# dashboard-pcbsch_aveon.net
KiCad netlist of a schematic drawn in EAGLE
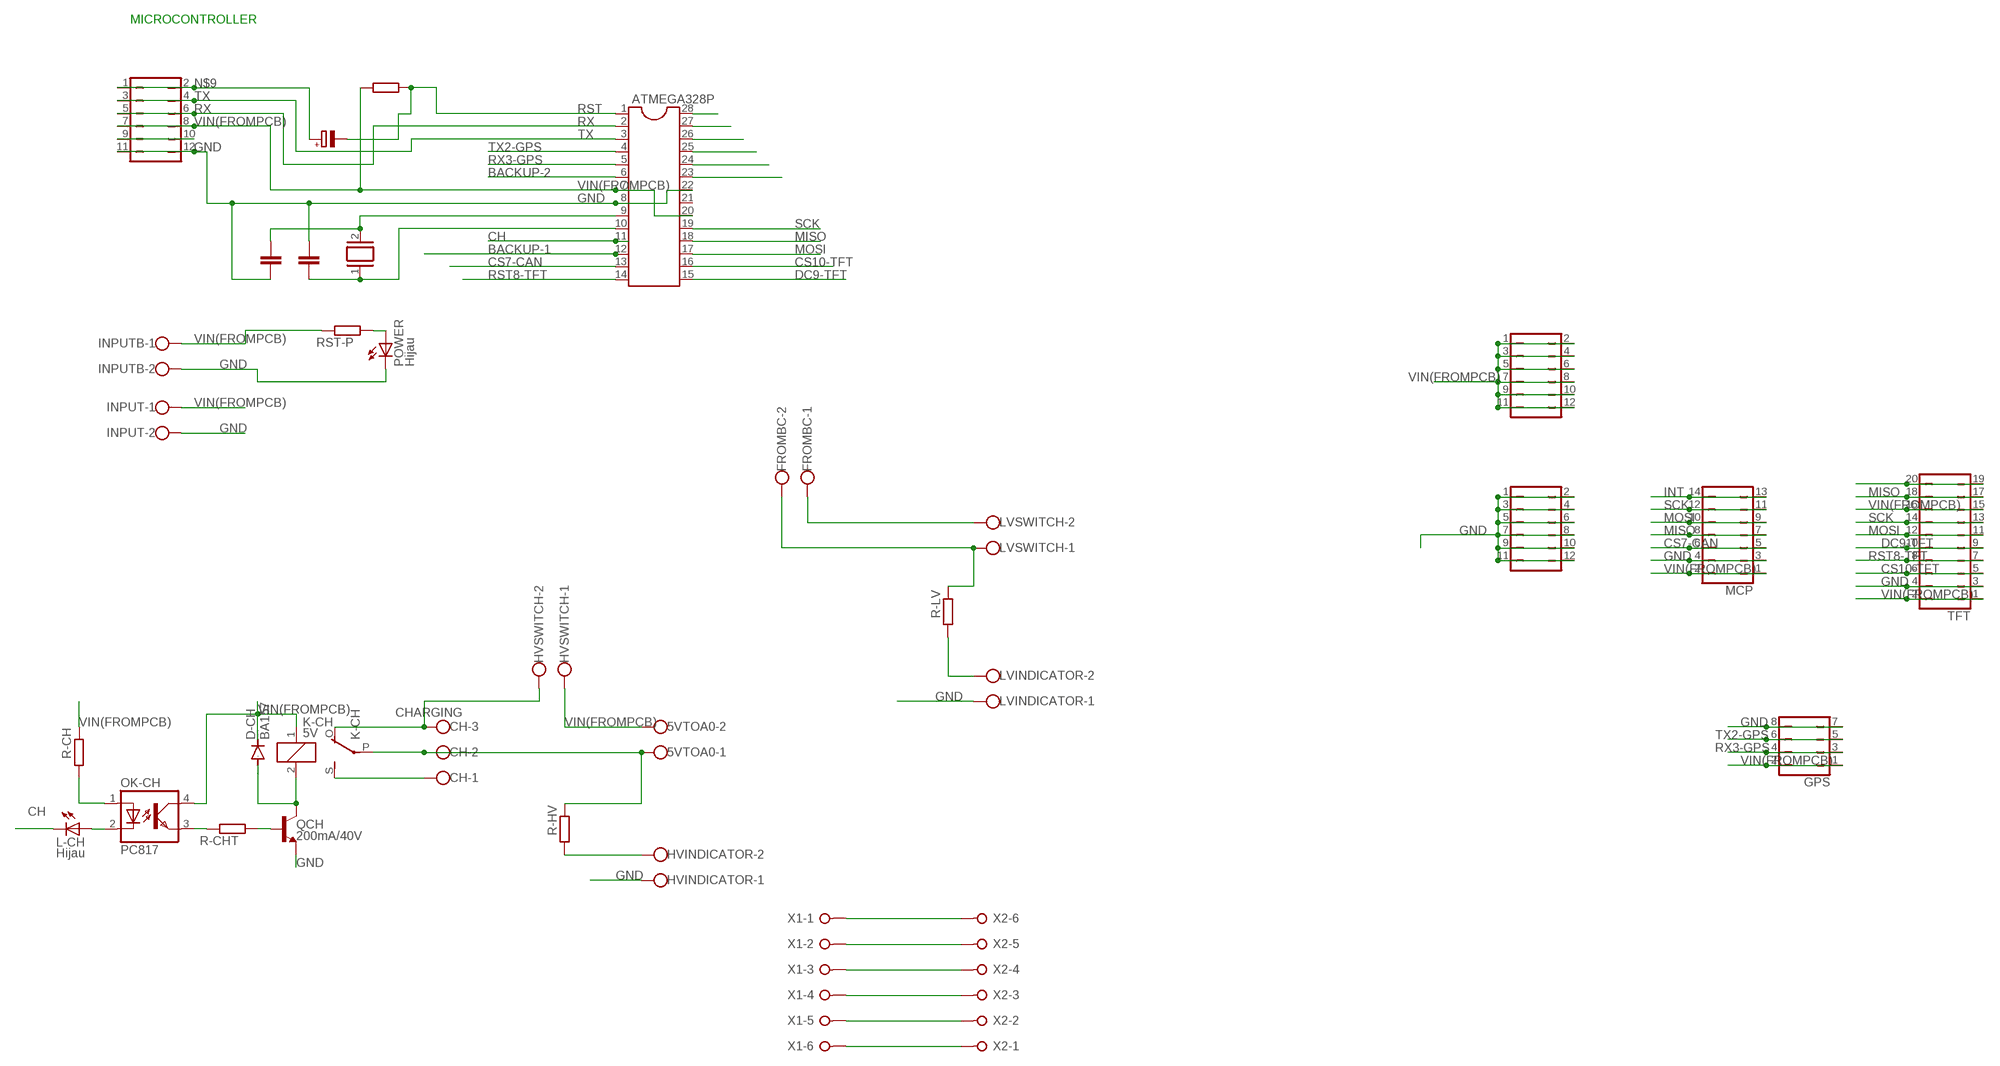
[diagram p0: schematic, sheet 1]

(export (version "E")
  (design (tool "Eeschema 10.0.6"))
  (components
    (comp (ref "5VTOA0")
      (value "W237-102")
      (footprint "eagle-import:W237-102")
      (fields (field (name "MPN") "237-102"))
      (libsource (lib "eagle-import") (part "W237-102"))
    )
    (comp (ref "ATMEGA328P")
      (value "DIL28-3")
      (footprint "eagle-import:DIL28-3")
      (libsource (lib "eagle-import") (part "DIL28-3"))
    )
    (comp (ref "C1")
      (value "C-EU025-030X050")
      (footprint "eagle-import:C025-030X050")
      (libsource (lib "eagle-import") (part "C-EU025-030X050"))
    )
    (comp (ref "C2")
      (value "C-EU025-030X050")
      (footprint "eagle-import:C025-030X050")
      (libsource (lib "eagle-import") (part "C-EU025-030X050"))
    )
    (comp (ref "CH")
      (value "CHARGING")
      (footprint "eagle-import:W237-103")
      (fields (field (name "MPN") "237-103"))
      (libsource (lib "eagle-import") (part "W237-103"))
    )
    (comp (ref "CRYSTAL")
      (value "XTAL/S")
      (footprint "eagle-import:QS")
      (libsource (lib "eagle-import") (part "XTAL/S"))
    )
    (comp (ref "D-CH")
      (value "BA157")
      (footprint "eagle-import:P1-10")
      (libsource (lib "eagle-import") (part "BA157"))
    )
    (comp (ref "FROMBC")
      (value "W237-102")
      (footprint "eagle-import:W237-102")
      (fields (field (name "MPN") "237-102"))
      (libsource (lib "eagle-import") (part "W237-102"))
    )
    (comp (ref "GPS")
      (value "JP4Q")
      (footprint "eagle-import:JP4Q")
      (libsource (lib "eagle-import") (part "JP4Q"))
    )
    (comp (ref "GROUND")
      (value "JP6Q")
      (footprint "eagle-import:JP6Q")
      (libsource (lib "eagle-import") (part "JP6Q"))
    )
    (comp (ref "HVINDICATOR")
      (value "W237-102")
      (footprint "eagle-import:W237-102")
      (fields (field (name "MPN") "237-102"))
      (libsource (lib "eagle-import") (part "W237-102"))
    )
    (comp (ref "HVSWITCH")
      (value "W237-102")
      (footprint "eagle-import:W237-102")
      (fields (field (name "MPN") "237-102"))
      (libsource (lib "eagle-import") (part "W237-102"))
    )
    (comp (ref "INPUT")
      (value "W237-102")
      (footprint "eagle-import:W237-102")
      (fields (field (name "MPN") "237-102"))
      (libsource (lib "eagle-import") (part "W237-102"))
    )
    (comp (ref "INPUTB")
      (value "W237-102")
      (footprint "eagle-import:W237-102")
      (fields (field (name "MPN") "237-102"))
      (libsource (lib "eagle-import") (part "W237-102"))
    )
    (comp (ref "K-CH")
      (value "5V")
      (footprint "eagle-import:ZF112")
      (libsource (lib "eagle-import") (part "ZF112"))
    )
    (comp (ref "L-CH")
      (value "Hijau")
      (footprint "eagle-import:LED3MM")
      (libsource (lib "eagle-import") (part "LED3MM"))
    )
    (comp (ref "LVINDICATOR")
      (value "W237-102")
      (footprint "eagle-import:W237-102")
      (fields (field (name "MPN") "237-102"))
      (libsource (lib "eagle-import") (part "W237-102"))
    )
    (comp (ref "LVSWITCH")
      (value "W237-102")
      (footprint "eagle-import:W237-102")
      (fields (field (name "MPN") "237-102"))
      (libsource (lib "eagle-import") (part "W237-102"))
    )
    (comp (ref "MCP")
      (value "JP7Q")
      (footprint "eagle-import:JP7Q")
      (libsource (lib "eagle-import") (part "JP7Q"))
    )
    (comp (ref "OK-CH")
      (value "PC817")
      (footprint "eagle-import:DIL04")
      (fields (field (name "MPN") "PC817X4J000F"))
      (libsource (lib "eagle-import") (part "PC817"))
    )
    (comp (ref "POWER")
      (value "Hijau")
      (footprint "eagle-import:LED3MM")
      (libsource (lib "eagle-import") (part "LED3MM"))
    )
    (comp (ref "PROGRAMMER")
      (value "JP6Q")
      (footprint "eagle-import:JP6Q")
      (libsource (lib "eagle-import") (part "JP6Q"))
    )
    (comp (ref "QCH")
      (value "200mA/40V")
      (footprint "eagle-import:TO-92")
      (libsource (lib "eagle-import") (part "TRANS_NPN-2N3904"))
    )
    (comp (ref "R-CH")
      (value "R-EU_0204/7")
      (footprint "eagle-import:0204_7")
      (libsource (lib "eagle-import") (part "R-EU_0204/7"))
    )
    (comp (ref "R-CHT")
      (value "R-EU_0204/7")
      (footprint "eagle-import:0204_7")
      (libsource (lib "eagle-import") (part "R-EU_0204/7"))
    )
    (comp (ref "R-HV")
      (value "R-EU_0204/7")
      (footprint "eagle-import:0204_7")
      (libsource (lib "eagle-import") (part "R-EU_0204/7"))
    )
    (comp (ref "R-LV")
      (value "R-EU_0204/7")
      (footprint "eagle-import:0204_7")
      (libsource (lib "eagle-import") (part "R-EU_0204/7"))
    )
    (comp (ref "RST-C")
      (value "CPOL-EUE2.5-6")
      (footprint "eagle-import:E2,5-6")
      (libsource (lib "eagle-import") (part "CPOL-EUE2.5-6"))
    )
    (comp (ref "RST-P")
      (value "R-EU_0204/7")
      (footprint "eagle-import:0204_7")
      (libsource (lib "eagle-import") (part "R-EU_0204/7"))
    )
    (comp (ref "RST-R")
      (value "R-EU_0204/7")
      (footprint "eagle-import:0204_7")
      (libsource (lib "eagle-import") (part "R-EU_0204/7"))
    )
    (comp (ref "TFT")
      (value "JP10Q")
      (footprint "eagle-import:JP10Q")
      (libsource (lib "eagle-import") (part "JP10Q"))
    )
    (comp (ref "VIN(FROMPC)")
      (value "JP6Q")
      (footprint "eagle-import:JP6Q")
      (libsource (lib "eagle-import") (part "JP6Q"))
    )
    (comp (ref "X1")
      (value "W237-06P")
      (footprint "eagle-import:W237-6P")
      (libsource (lib "eagle-import") (part "W237-06P"))
    )
    (comp (ref "X2")
      (value "W237-06P")
      (footprint "eagle-import:W237-6P")
      (libsource (lib "eagle-import") (part "W237-06P"))
    )
  )
  (nets
    (net (code "1") (name "/BACKUP-1") (class "Default")
      (node (ref "ATMEGA328P") (pin "12") (pinfunction "12_12") (pintype "passive"))
    )
    (net (code "2") (name "/BACKUP-2") (class "Default")
      (node (ref "ATMEGA328P") (pin "6") (pinfunction "6_6") (pintype "passive"))
    )
    (net (code "3") (name "/CH") (class "Default")
      (node (ref "ATMEGA328P") (pin "11") (pinfunction "11_11") (pintype "passive"))
      (node (ref "L-CH") (pin "K") (pinfunction "C_K") (pintype "passive"))
    )
    (net (code "4") (name "/CS7-CAN") (class "Default")
      (node (ref "ATMEGA328P") (pin "13") (pinfunction "13_13") (pintype "passive"))
      (node (ref "MCP") (pin "5") (pinfunction "5_5") (pintype "passive"))
      (node (ref "MCP") (pin "6") (pinfunction "6_6") (pintype "passive"))
    )
    (net (code "5") (name "/CS10-TFT") (class "Default")
      (node (ref "ATMEGA328P") (pin "16") (pinfunction "16_16") (pintype "passive"))
      (node (ref "TFT") (pin "5") (pinfunction "5_5") (pintype "passive"))
      (node (ref "TFT") (pin "6") (pinfunction "6_6") (pintype "passive"))
    )
    (net (code "6") (name "/DC9-TFT") (class "Default")
      (node (ref "ATMEGA328P") (pin "15") (pinfunction "15_15") (pintype "passive"))
      (node (ref "TFT") (pin "10") (pinfunction "10_10") (pintype "passive"))
      (node (ref "TFT") (pin "9") (pinfunction "9_9") (pintype "passive"))
    )
    (net (code "7") (name "/GND") (class "Default")
      (node (ref "ATMEGA328P") (pin "22") (pinfunction "22_22") (pintype "passive"))
      (node (ref "ATMEGA328P") (pin "8") (pinfunction "8_8") (pintype "passive"))
      (node (ref "C1") (pin "1") (pinfunction "1_1") (pintype "passive"))
      (node (ref "C2") (pin "2") (pinfunction "2_2") (pintype "passive"))
      (node (ref "GPS") (pin "7") (pinfunction "7_7") (pintype "passive"))
      (node (ref "GPS") (pin "8") (pinfunction "8_8") (pintype "passive"))
      (node (ref "GROUND") (pin "1") (pinfunction "1_1") (pintype "passive"))
      (node (ref "GROUND") (pin "10") (pinfunction "10_10") (pintype "passive"))
      (node (ref "GROUND") (pin "11") (pinfunction "11_11") (pintype "passive"))
      (node (ref "GROUND") (pin "12") (pinfunction "12_12") (pintype "passive"))
      (node (ref "GROUND") (pin "2") (pinfunction "2_2") (pintype "passive"))
      (node (ref "GROUND") (pin "3") (pinfunction "3_3") (pintype "passive"))
      (node (ref "GROUND") (pin "4") (pinfunction "4_4") (pintype "passive"))
      (node (ref "GROUND") (pin "5") (pinfunction "5_5") (pintype "passive"))
      (node (ref "GROUND") (pin "6") (pinfunction "6_6") (pintype "passive"))
      (node (ref "GROUND") (pin "7") (pinfunction "7_7") (pintype "passive"))
      (node (ref "GROUND") (pin "8") (pinfunction "8_8") (pintype "passive"))
      (node (ref "GROUND") (pin "9") (pinfunction "9_9") (pintype "passive"))
      (node (ref "HVINDICATOR") (pin "1") (pinfunction "KL_1") (pintype "passive"))
      (node (ref "INPUT") (pin "2") (pinfunction "KL_2") (pintype "passive"))
      (node (ref "INPUTB") (pin "2") (pinfunction "KL_2") (pintype "passive"))
      (node (ref "LVINDICATOR") (pin "1") (pinfunction "KL_1") (pintype "passive"))
      (node (ref "MCP") (pin "3") (pinfunction "3_3") (pintype "passive"))
      (node (ref "MCP") (pin "4") (pinfunction "4_4") (pintype "passive"))
      (node (ref "POWER") (pin "K") (pinfunction "C_K") (pintype "passive"))
      (node (ref "PROGRAMMER") (pin "11") (pinfunction "11_11") (pintype "passive"))
      (node (ref "PROGRAMMER") (pin "12") (pinfunction "12_12") (pintype "passive"))
      (node (ref "QCH") (pin "1") (pinfunction "E_1") (pintype "passive"))
      (node (ref "TFT") (pin "3") (pinfunction "3_3") (pintype "passive"))
      (node (ref "TFT") (pin "4") (pinfunction "4_4") (pintype "passive"))
    )
    (net (code "8") (name "/INT") (class "Default")
      (node (ref "MCP") (pin "13") (pinfunction "13_13") (pintype "passive"))
      (node (ref "MCP") (pin "14") (pinfunction "14_14") (pintype "passive"))
    )
    (net (code "9") (name "/MISO") (class "Default")
      (node (ref "ATMEGA328P") (pin "18") (pinfunction "18_18") (pintype "passive"))
      (node (ref "MCP") (pin "7") (pinfunction "7_7") (pintype "passive"))
      (node (ref "MCP") (pin "8") (pinfunction "8_8") (pintype "passive"))
      (node (ref "TFT") (pin "17") (pinfunction "17_17") (pintype "passive"))
      (node (ref "TFT") (pin "18") (pinfunction "18_18") (pintype "passive"))
    )
    (net (code "10") (name "/MOSI") (class "Default")
      (node (ref "ATMEGA328P") (pin "17") (pinfunction "17_17") (pintype "passive"))
      (node (ref "MCP") (pin "10") (pinfunction "10_10") (pintype "passive"))
      (node (ref "MCP") (pin "9") (pinfunction "9_9") (pintype "passive"))
      (node (ref "TFT") (pin "11") (pinfunction "11_11") (pintype "passive"))
      (node (ref "TFT") (pin "12") (pinfunction "12_12") (pintype "passive"))
    )
    (net (code "11") (name "/N$9") (class "Default")
      (node (ref "PROGRAMMER") (pin "1") (pinfunction "1_1") (pintype "passive"))
      (node (ref "PROGRAMMER") (pin "2") (pinfunction "2_2") (pintype "passive"))
      (node (ref "RST-C") (pin "+") (pinfunction "+_+") (pintype "passive"))
    )
    (net (code "12") (name "/RST") (class "Default")
      (node (ref "ATMEGA328P") (pin "1") (pinfunction "1_1") (pintype "passive"))
      (node (ref "RST-C") (pin "-") (pinfunction "-_-") (pintype "passive"))
      (node (ref "RST-R") (pin "2") (pinfunction "2_2") (pintype "passive"))
    )
    (net (code "13") (name "/RST8-TFT") (class "Default")
      (node (ref "ATMEGA328P") (pin "14") (pinfunction "14_14") (pintype "passive"))
      (node (ref "TFT") (pin "7") (pinfunction "7_7") (pintype "passive"))
      (node (ref "TFT") (pin "8") (pinfunction "8_8") (pintype "passive"))
    )
    (net (code "14") (name "/RX") (class "Default")
      (node (ref "ATMEGA328P") (pin "2") (pinfunction "2_2") (pintype "passive"))
      (node (ref "PROGRAMMER") (pin "5") (pinfunction "5_5") (pintype "passive"))
      (node (ref "PROGRAMMER") (pin "6") (pinfunction "6_6") (pintype "passive"))
    )
    (net (code "15") (name "/RX3-GPS") (class "Default")
      (node (ref "ATMEGA328P") (pin "5") (pinfunction "5_5") (pintype "passive"))
      (node (ref "GPS") (pin "3") (pinfunction "3_3") (pintype "passive"))
      (node (ref "GPS") (pin "4") (pinfunction "4_4") (pintype "passive"))
    )
    (net (code "16") (name "/SCK") (class "Default")
      (node (ref "ATMEGA328P") (pin "19") (pinfunction "19_19") (pintype "passive"))
      (node (ref "MCP") (pin "11") (pinfunction "11_11") (pintype "passive"))
      (node (ref "MCP") (pin "12") (pinfunction "12_12") (pintype "passive"))
      (node (ref "TFT") (pin "13") (pinfunction "13_13") (pintype "passive"))
      (node (ref "TFT") (pin "14") (pinfunction "14_14") (pintype "passive"))
    )
    (net (code "17") (name "/TX") (class "Default")
      (node (ref "ATMEGA328P") (pin "3") (pinfunction "3_3") (pintype "passive"))
      (node (ref "PROGRAMMER") (pin "3") (pinfunction "3_3") (pintype "passive"))
      (node (ref "PROGRAMMER") (pin "4") (pinfunction "4_4") (pintype "passive"))
    )
    (net (code "18") (name "/TX2-GPS") (class "Default")
      (node (ref "ATMEGA328P") (pin "4") (pinfunction "4_4") (pintype "passive"))
      (node (ref "GPS") (pin "5") (pinfunction "5_5") (pintype "passive"))
      (node (ref "GPS") (pin "6") (pinfunction "6_6") (pintype "passive"))
    )
    (net (code "19") (name "/VIN(FROMPCB)") (class "Default")
      (node (ref "5VTOA0") (pin "2") (pinfunction "KL_2") (pintype "passive"))
      (node (ref "ATMEGA328P") (pin "20") (pinfunction "20_20") (pintype "passive"))
      (node (ref "ATMEGA328P") (pin "7") (pinfunction "7_7") (pintype "passive"))
      (node (ref "D-CH") (pin "C") (pinfunction "C_C") (pintype "passive"))
      (node (ref "GPS") (pin "1") (pinfunction "1_1") (pintype "passive"))
      (node (ref "GPS") (pin "2") (pinfunction "2_2") (pintype "passive"))
      (node (ref "HVSWITCH") (pin "1") (pinfunction "KL_1") (pintype "passive"))
      (node (ref "INPUT") (pin "1") (pinfunction "KL_1") (pintype "passive"))
      (node (ref "INPUTB") (pin "1") (pinfunction "KL_1") (pintype "passive"))
      (node (ref "K-CH") (pin "1") (pinfunction "1_1") (pintype "passive"))
      (node (ref "MCP") (pin "1") (pinfunction "1_1") (pintype "passive"))
      (node (ref "MCP") (pin "2") (pinfunction "2_2") (pintype "passive"))
      (node (ref "OK-CH") (pin "4") (pinfunction "COL_4") (pintype "passive"))
      (node (ref "PROGRAMMER") (pin "7") (pinfunction "7_7") (pintype "passive"))
      (node (ref "PROGRAMMER") (pin "8") (pinfunction "8_8") (pintype "passive"))
      (node (ref "R-CH") (pin "2") (pinfunction "2_2") (pintype "passive"))
      (node (ref "RST-P") (pin "2") (pinfunction "2_2") (pintype "passive"))
      (node (ref "RST-R") (pin "1") (pinfunction "1_1") (pintype "passive"))
      (node (ref "TFT") (pin "1") (pinfunction "1_1") (pintype "passive"))
      (node (ref "TFT") (pin "15") (pinfunction "15_15") (pintype "passive"))
      (node (ref "TFT") (pin "16") (pinfunction "16_16") (pintype "passive"))
      (node (ref "TFT") (pin "2") (pinfunction "2_2") (pintype "passive"))
      (node (ref "VIN(FROMPC)") (pin "1") (pinfunction "1_1") (pintype "passive"))
      (node (ref "VIN(FROMPC)") (pin "10") (pinfunction "10_10") (pintype "passive"))
      (node (ref "VIN(FROMPC)") (pin "11") (pinfunction "11_11") (pintype "passive"))
      (node (ref "VIN(FROMPC)") (pin "12") (pinfunction "12_12") (pintype "passive"))
      (node (ref "VIN(FROMPC)") (pin "2") (pinfunction "2_2") (pintype "passive"))
      (node (ref "VIN(FROMPC)") (pin "3") (pinfunction "3_3") (pintype "passive"))
      (node (ref "VIN(FROMPC)") (pin "4") (pinfunction "4_4") (pintype "passive"))
      (node (ref "VIN(FROMPC)") (pin "5") (pinfunction "5_5") (pintype "passive"))
      (node (ref "VIN(FROMPC)") (pin "6") (pinfunction "6_6") (pintype "passive"))
      (node (ref "VIN(FROMPC)") (pin "7") (pinfunction "7_7") (pintype "passive"))
      (node (ref "VIN(FROMPC)") (pin "8") (pinfunction "8_8") (pintype "passive"))
      (node (ref "VIN(FROMPC)") (pin "9") (pinfunction "9_9") (pintype "passive"))
    )
    (net (code "20") (name "Net-(5VTOA0A-KL)") (class "Default")
      (node (ref "5VTOA0") (pin "1") (pinfunction "KL_1") (pintype "passive"))
      (node (ref "CH") (pin "2") (pinfunction "KL_2") (pintype "passive"))
      (node (ref "K-CH") (pin "P") (pinfunction "P_P") (pintype "passive"))
      (node (ref "R-HV") (pin "2") (pinfunction "2_2") (pintype "passive"))
    )
    (net (code "21") (name "Net-(ATMEGA328P-Pad9)") (class "Default")
      (node (ref "ATMEGA328P") (pin "9") (pinfunction "9_9") (pintype "passive"))
      (node (ref "C1") (pin "2") (pinfunction "2_2") (pintype "passive"))
      (node (ref "CRYSTAL") (pin "2") (pinfunction "2_2") (pintype "passive"))
    )
    (net (code "22") (name "Net-(ATMEGA328P-Pad10)") (class "Default")
      (node (ref "ATMEGA328P") (pin "10") (pinfunction "10_10") (pintype "passive"))
      (node (ref "C2") (pin "1") (pinfunction "1_1") (pintype "passive"))
      (node (ref "CRYSTAL") (pin "1") (pinfunction "1_1") (pintype "passive"))
    )
    (net (code "23") (name "Net-(CHA-KL)") (class "Default")
      (node (ref "CH") (pin "1") (pinfunction "KL_1") (pintype "passive"))
      (node (ref "K-CH") (pin "S") (pinfunction "S_S") (pintype "passive"))
    )
    (net (code "24") (name "Net-(CHC-KL)") (class "Default")
      (node (ref "CH") (pin "3") (pinfunction "KL_3") (pintype "passive"))
      (node (ref "HVSWITCH") (pin "2") (pinfunction "KL_2") (pintype "passive"))
      (node (ref "K-CH") (pin "O") (pinfunction "O_O") (pintype "passive"))
    )
    (net (code "25") (name "Net-(FROMBCA-KL)") (class "Default")
      (node (ref "FROMBC") (pin "1") (pinfunction "KL_1") (pintype "passive"))
      (node (ref "LVSWITCH") (pin "2") (pinfunction "KL_2") (pintype "passive"))
    )
    (net (code "26") (name "Net-(FROMBCB-KL)") (class "Default")
      (node (ref "FROMBC") (pin "2") (pinfunction "KL_2") (pintype "passive"))
      (node (ref "LVSWITCH") (pin "1") (pinfunction "KL_1") (pintype "passive"))
      (node (ref "R-LV") (pin "2") (pinfunction "2_2") (pintype "passive"))
    )
    (net (code "27") (name "Net-(HVINDICATORB-KL)") (class "Default")
      (node (ref "HVINDICATOR") (pin "2") (pinfunction "KL_2") (pintype "passive"))
      (node (ref "R-HV") (pin "1") (pinfunction "1_1") (pintype "passive"))
    )
    (net (code "28") (name "Net-(LVINDICATORB-KL)") (class "Default")
      (node (ref "LVINDICATOR") (pin "2") (pinfunction "KL_2") (pintype "passive"))
      (node (ref "R-LV") (pin "1") (pinfunction "1_1") (pintype "passive"))
    )
    (net (code "29") (name "Net-(OK-CH-A)") (class "Default")
      (node (ref "OK-CH") (pin "1") (pinfunction "A_1") (pintype "passive"))
      (node (ref "R-CH") (pin "1") (pinfunction "1_1") (pintype "passive"))
    )
    (net (code "30") (name "Net-(OK-CH-C)") (class "Default")
      (node (ref "L-CH") (pin "A") (pinfunction "A_A") (pintype "passive"))
      (node (ref "OK-CH") (pin "2") (pinfunction "C_2") (pintype "passive"))
    )
    (net (code "31") (name "Net-(OK-CH-EMIT)") (class "Default")
      (node (ref "OK-CH") (pin "3") (pinfunction "EMIT_3") (pintype "passive"))
      (node (ref "R-CHT") (pin "2") (pinfunction "2_2") (pintype "passive"))
    )
    (net (code "32") (name "Net-(POWER-PadA)") (class "Default")
      (node (ref "POWER") (pin "A") (pinfunction "A_A") (pintype "passive"))
      (node (ref "RST-P") (pin "1") (pinfunction "1_1") (pintype "passive"))
    )
    (net (code "33") (name "Net-(PROGRAMMER-Pad10)") (class "Default")
      (node (ref "PROGRAMMER") (pin "10") (pinfunction "10_10") (pintype "passive"))
      (node (ref "PROGRAMMER") (pin "9") (pinfunction "9_9") (pintype "passive"))
    )
    (net (code "34") (name "Net-(QCH-B)") (class "Default")
      (node (ref "QCH") (pin "2") (pinfunction "B_2") (pintype "passive"))
      (node (ref "R-CHT") (pin "1") (pinfunction "1_1") (pintype "passive"))
    )
    (net (code "35") (name "Net-(QCH-C)") (class "Default")
      (node (ref "D-CH") (pin "A") (pinfunction "A_A") (pintype "passive"))
      (node (ref "K-CH") (pin "2") (pinfunction "2_2") (pintype "passive"))
      (node (ref "QCH") (pin "3") (pinfunction "C_3") (pintype "passive"))
    )
    (net (code "36") (name "Net-(TFT-Pad19)") (class "Default")
      (node (ref "TFT") (pin "19") (pinfunction "19_19") (pintype "passive"))
      (node (ref "TFT") (pin "20") (pinfunction "20_20") (pintype "passive"))
    )
    (net (code "37") (name "Net-(X1A-KL)") (class "Default")
      (node (ref "X1") (pin "1") (pinfunction "KL_1") (pintype "passive"))
      (node (ref "X2") (pin "6") (pinfunction "KL_6") (pintype "passive"))
    )
    (net (code "38") (name "Net-(X1B-KL)") (class "Default")
      (node (ref "X1") (pin "2") (pinfunction "KL_2") (pintype "passive"))
      (node (ref "X2") (pin "5") (pinfunction "KL_5") (pintype "passive"))
    )
    (net (code "39") (name "Net-(X1C-KL)") (class "Default")
      (node (ref "X1") (pin "3") (pinfunction "KL_3") (pintype "passive"))
      (node (ref "X2") (pin "4") (pinfunction "KL_4") (pintype "passive"))
    )
    (net (code "40") (name "Net-(X1D-KL)") (class "Default")
      (node (ref "X1") (pin "4") (pinfunction "KL_4") (pintype "passive"))
      (node (ref "X2") (pin "3") (pinfunction "KL_3") (pintype "passive"))
    )
    (net (code "41") (name "Net-(X1E-KL)") (class "Default")
      (node (ref "X1") (pin "5") (pinfunction "KL_5") (pintype "passive"))
      (node (ref "X2") (pin "2") (pinfunction "KL_2") (pintype "passive"))
    )
    (net (code "42") (name "Net-(X1F-KL)") (class "Default")
      (node (ref "X1") (pin "6") (pinfunction "KL_6") (pintype "passive"))
      (node (ref "X2") (pin "1") (pinfunction "KL_1") (pintype "passive"))
    )
    (net (code "43") (name "unconnected-(ATMEGA328P-Pad21)") (class "Default")
      (node (ref "ATMEGA328P") (pin "21") (pinfunction "21_21") (pintype "passive"))
    )
    (net (code "44") (name "unconnected-(ATMEGA328P-Pad23)") (class "Default")
      (node (ref "ATMEGA328P") (pin "23") (pinfunction "23_23") (pintype "passive"))
    )
    (net (code "45") (name "unconnected-(ATMEGA328P-Pad24)") (class "Default")
      (node (ref "ATMEGA328P") (pin "24") (pinfunction "24_24") (pintype "passive"))
    )
    (net (code "46") (name "unconnected-(ATMEGA328P-Pad25)") (class "Default")
      (node (ref "ATMEGA328P") (pin "25") (pinfunction "25_25") (pintype "passive"))
    )
    (net (code "47") (name "unconnected-(ATMEGA328P-Pad26)") (class "Default")
      (node (ref "ATMEGA328P") (pin "26") (pinfunction "26_26") (pintype "passive"))
    )
    (net (code "48") (name "unconnected-(ATMEGA328P-Pad27)") (class "Default")
      (node (ref "ATMEGA328P") (pin "27") (pinfunction "27_27") (pintype "passive"))
    )
    (net (code "49") (name "unconnected-(ATMEGA328P-Pad28)") (class "Default")
      (node (ref "ATMEGA328P") (pin "28") (pinfunction "28_28") (pintype "passive"))
    )
  )
)
